# StripNanite.net
KiCad netlist of a schematic drawn in EAGLE
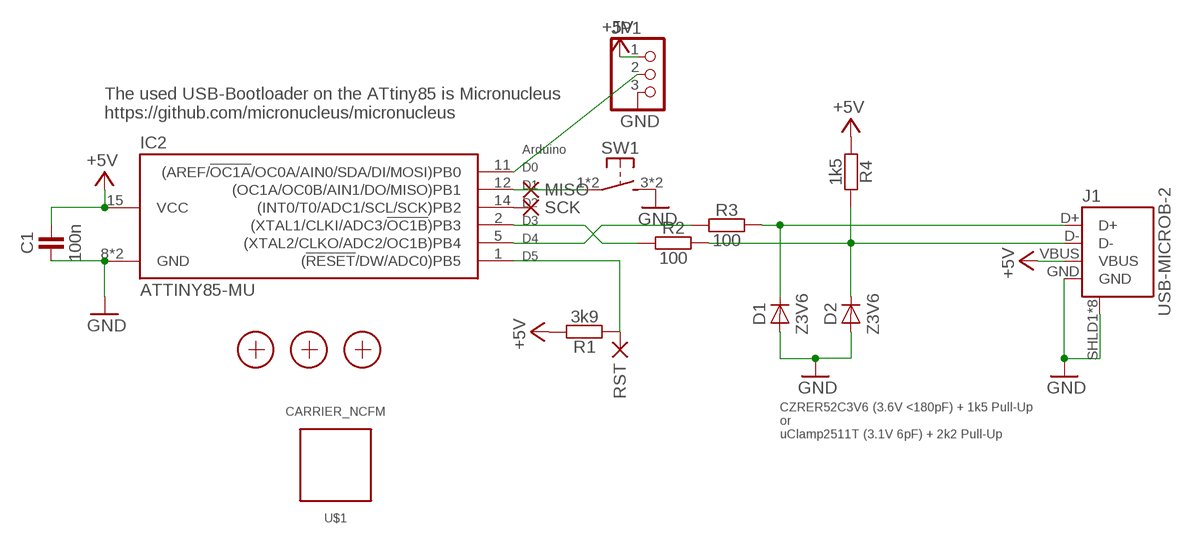
[diagram p0: schematic, sheet 1]

(export (version "E")
  (design (tool "Eeschema 10.0.6"))
  (components
    (comp (ref "C1")
      (value "100n")
      (footprint "eagle-import:C0402")
      (libsource (lib "eagle-import") (part "CAPACITOR-0402"))
    )
    (comp (ref "D1")
      (value "Z3V6")
      (footprint "eagle-import:SOD882")
      (libsource (lib "eagle-import") (part "DIODE-SOD882"))
    )
    (comp (ref "D2")
      (value "Z3V6")
      (footprint "eagle-import:SOD882")
      (libsource (lib "eagle-import") (part "DIODE-SOD882"))
    )
    (comp (ref "IC2")
      (value "ATTINY85-MU")
      (footprint "eagle-import:QFN20-PAD")
      (libsource (lib "eagle-import") (part "ATTINY85-MU"))
    )
    (comp (ref "J1")
      (value "USB-MICROB-2")
      (footprint "eagle-import:USB-MICROB-10118194")
      (libsource (lib "eagle-import") (part "USB-MICROB-2"))
    )
    (comp (ref "JP1")
      (value "PINHD-1X3")
      (footprint "eagle-import:1X03")
      (libsource (lib "eagle-import") (part "PINHD-1X3"))
    )
    (comp (ref "MISO")
      (value "PAD-1.0")
      (footprint "eagle-import:PAD-1.0")
      (libsource (lib "eagle-import") (part "PAD-1.0"))
    )
    (comp (ref "R1")
      (value "3k9")
      (footprint "eagle-import:C0402")
      (libsource (lib "eagle-import") (part "RESISTOR-0402"))
    )
    (comp (ref "R2")
      (value "100")
      (footprint "eagle-import:C0402")
      (libsource (lib "eagle-import") (part "RESISTOR-0402"))
    )
    (comp (ref "R3")
      (value "100")
      (footprint "eagle-import:C0402")
      (libsource (lib "eagle-import") (part "RESISTOR-0402"))
    )
    (comp (ref "R4")
      (value "1k5")
      (footprint "eagle-import:C0402")
      (libsource (lib "eagle-import") (part "RESISTOR-0402"))
    )
    (comp (ref "RST")
      (value "PAD-1.0")
      (footprint "eagle-import:PAD-1.0")
      (libsource (lib "eagle-import") (part "PAD-1.0"))
    )
    (comp (ref "SCK")
      (value "PAD-1.0")
      (footprint "eagle-import:PAD-1.0")
      (libsource (lib "eagle-import") (part "PAD-1.0"))
    )
    (comp (ref "SW1")
      (value "SW-TACTILE-PTS840P")
      (footprint "eagle-import:PTS840P")
      (libsource (lib "eagle-import") (part "SW-TACTILE-PTS840P"))
    )
    (comp (ref "U$1")
      (value "CARRIER_NCFM")
      (footprint "eagle-import:FM")
      (libsource (lib "eagle-import") (part "CARRIER_NCFM"))
    )
    (comp (ref "X1")
      (value "PASSER-07")
      (footprint "eagle-import:PASSER_07MM")
      (libsource (lib "eagle-import") (part "PASSER-07"))
    )
    (comp (ref "X2")
      (value "PASSER-07")
      (footprint "eagle-import:PASSER_07MM")
      (libsource (lib "eagle-import") (part "PASSER-07"))
    )
    (comp (ref "X3")
      (value "PASSER-07")
      (footprint "eagle-import:PASSER_07MM")
      (libsource (lib "eagle-import") (part "PASSER-07"))
    )
  )
  (nets
    (net (code "1") (name "+5V") (class "Default")
      (node (ref "C1") (pin "2") (pinfunction "2_2") (pintype "passive"))
      (node (ref "IC2") (pin "15") (pinfunction "VCC_15") (pintype "power_in"))
      (node (ref "J1") (pin "VBUS") (pinfunction "VBUS_VBUS") (pintype "power_in"))
      (node (ref "JP1") (pin "1") (pinfunction "1_1") (pintype "passive"))
      (node (ref "R1") (pin "2") (pinfunction "2_2") (pintype "passive"))
      (node (ref "R4") (pin "1") (pinfunction "1_1") (pintype "passive"))
    )
    (net (code "2") (name "GND") (class "Default")
      (node (ref "C1") (pin "1") (pinfunction "1_1") (pintype "passive"))
      (node (ref "D1") (pin "A") (pinfunction "A_A") (pintype "passive"))
      (node (ref "D2") (pin "A") (pinfunction "A_A") (pintype "passive"))
      (node (ref "IC2") (pin "8") (pinfunction "GND_8") (pintype "power_in"))
      (node (ref "IC2") (pin "TP") (pinfunction "GND_TP") (pintype "power_in"))
      (node (ref "J1") (pin "GND") (pinfunction "GND_GND") (pintype "power_in"))
      (node (ref "J1") (pin "SHLD1") (pinfunction "SHIELD_SHLD1") (pintype "passive"))
      (node (ref "J1") (pin "SHLD2") (pinfunction "SHIELD_SHLD2") (pintype "passive"))
      (node (ref "J1") (pin "SHLD3") (pinfunction "SHIELD_SHLD3") (pintype "passive"))
      (node (ref "J1") (pin "SHLD4") (pinfunction "SHIELD_SHLD4") (pintype "passive"))
      (node (ref "J1") (pin "SHLD5") (pinfunction "SHIELD_SHLD5") (pintype "passive"))
      (node (ref "J1") (pin "SHLD6") (pinfunction "SHIELD_SHLD6") (pintype "passive"))
      (node (ref "J1") (pin "SHLD7") (pinfunction "SHIELD_SHLD7") (pintype "passive"))
      (node (ref "J1") (pin "SHLD8") (pinfunction "SHIELD_SHLD8") (pintype "passive"))
      (node (ref "JP1") (pin "3") (pinfunction "3_3") (pintype "passive"))
      (node (ref "SW1") (pin "3") (pinfunction "S1_3") (pintype "passive"))
      (node (ref "SW1") (pin "4") (pinfunction "S1_4") (pintype "passive"))
    )
    (net (code "3") (name "Net-(D1-PadC)") (class "Default")
      (node (ref "D1") (pin "C") (pinfunction "C_C") (pintype "passive"))
      (node (ref "J1") (pin "D+") (pinfunction "D+_D+") (pintype "bidirectional"))
      (node (ref "R3") (pin "2") (pinfunction "2_2") (pintype "passive"))
    )
    (net (code "4") (name "Net-(D2-PadC)") (class "Default")
      (node (ref "D2") (pin "C") (pinfunction "C_C") (pintype "passive"))
      (node (ref "J1") (pin "D-") (pinfunction "D-_D-") (pintype "bidirectional"))
      (node (ref "R2") (pin "2") (pinfunction "2_2") (pintype "passive"))
      (node (ref "R4") (pin "2") (pinfunction "2_2") (pintype "passive"))
    )
    (net (code "5") (name "Net-(IC2-(AREF{slash}~{OC1A}{slash}OC0A{slash}AIN0{slash}SDA{slash}DI{slash}MOSI)PB0)") (class "Default")
      (node (ref "IC2") (pin "11") (pinfunction "(AREF/~{OC1A}/OC0A/AIN0/SDA/DI/MOSI)PB0_11") (pintype "bidirectional"))
      (node (ref "JP1") (pin "2") (pinfunction "2_2") (pintype "passive"))
    )
    (net (code "6") (name "Net-(IC2-(INT0{slash}T0{slash}ADC1{slash}SCL{slash}SCK)PB2)") (class "Default")
      (node (ref "IC2") (pin "14") (pinfunction "(INT0/T0/ADC1/SCL/SCK)PB2_14") (pintype "bidirectional"))
      (node (ref "SCK") (pin "1") (pinfunction "P_1") (pintype "passive"))
    )
    (net (code "7") (name "Net-(IC2-(OC1A{slash}OC0B{slash}AIN1{slash}DO{slash}MISO)PB1)") (class "Default")
      (node (ref "IC2") (pin "12") (pinfunction "(OC1A/OC0B/AIN1/DO/MISO)PB1_12") (pintype "bidirectional"))
      (node (ref "MISO") (pin "1") (pinfunction "P_1") (pintype "passive"))
      (node (ref "SW1") (pin "1") (pinfunction "P1_1") (pintype "passive"))
      (node (ref "SW1") (pin "2") (pinfunction "P1_2") (pintype "passive"))
    )
    (net (code "8") (name "Net-(IC2-(XTAL1{slash}CLKI{slash}ADC3{slash}~{OC1B})PB3)") (class "Default")
      (node (ref "IC2") (pin "2") (pinfunction "(XTAL1/CLKI/ADC3/~{OC1B})PB3_2") (pintype "bidirectional"))
      (node (ref "R2") (pin "1") (pinfunction "1_1") (pintype "passive"))
    )
    (net (code "9") (name "Net-(IC2-(XTAL2{slash}CLKO{slash}ADC2{slash}OC1B)PB4)") (class "Default")
      (node (ref "IC2") (pin "5") (pinfunction "(XTAL2/CLKO/ADC2/OC1B)PB4_5") (pintype "bidirectional"))
      (node (ref "R3") (pin "1") (pinfunction "1_1") (pintype "passive"))
    )
    (net (code "10") (name "Net-(IC2-(~{RESET}{slash}DW{slash}ADC0)PB5)") (class "Default")
      (node (ref "IC2") (pin "1") (pinfunction "(~{RESET}/DW/ADC0)PB5_1") (pintype "bidirectional"))
      (node (ref "R1") (pin "1") (pinfunction "1_1") (pintype "passive"))
      (node (ref "RST") (pin "1") (pinfunction "P_1") (pintype "passive"))
    )
  )
)
